# Page07_CPU_PHY.net
KiCad netlist of a schematic drawn in Altium Designer
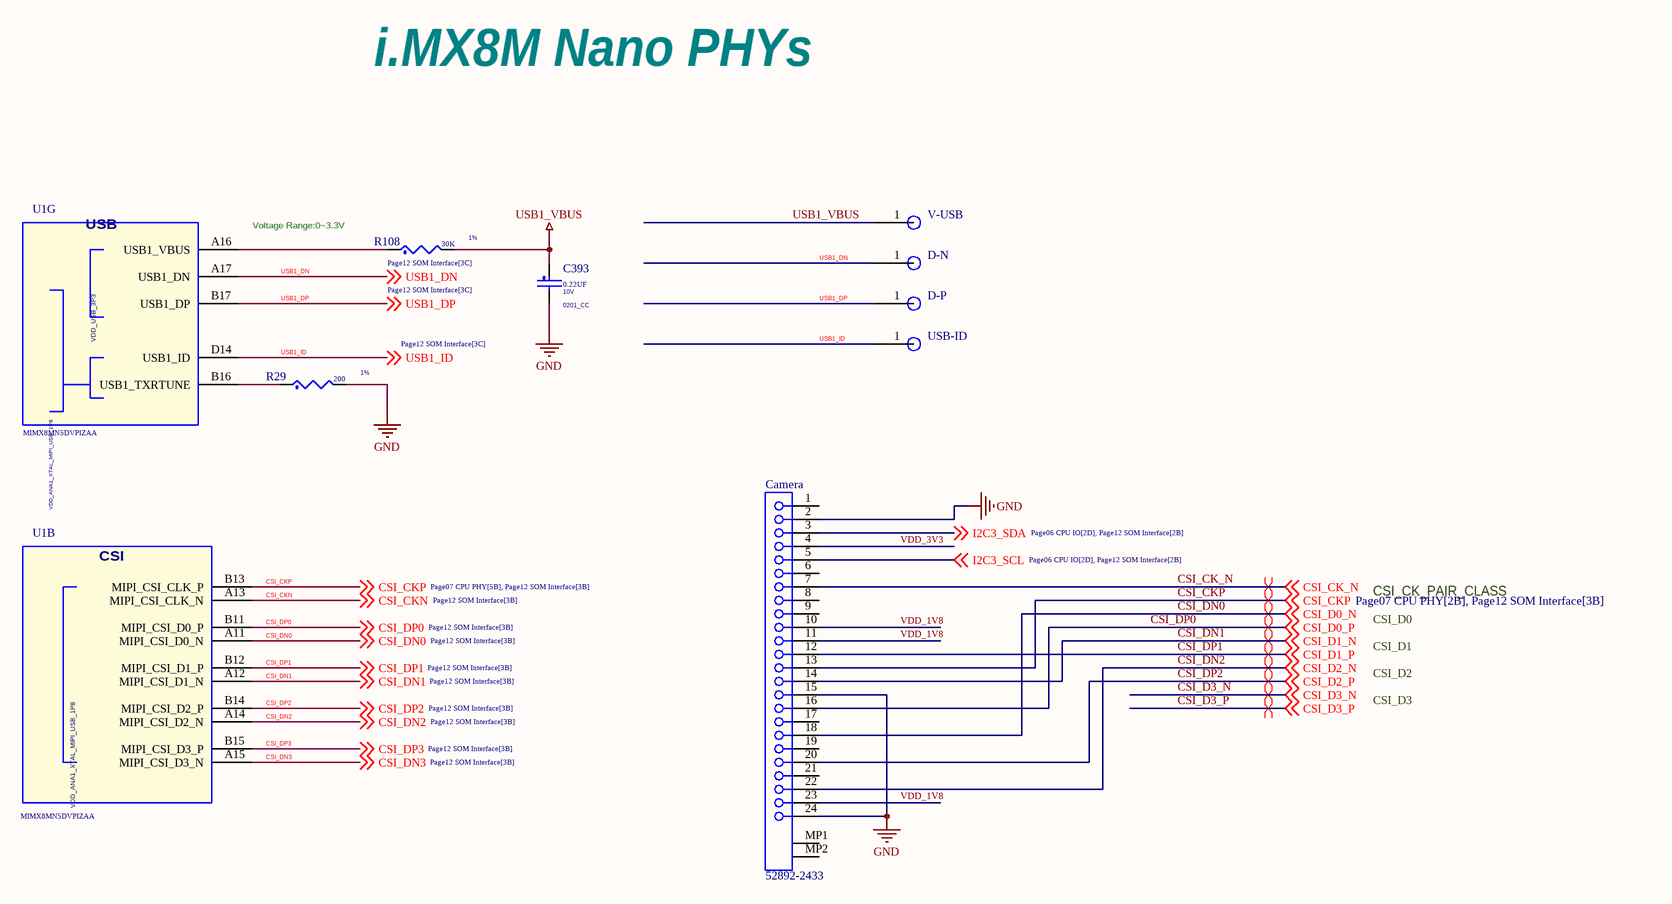
[diagram p0: Page07 CPU PHY.SchDoc]

(export (version "E")
  (design (tool "Eeschema 10.0.6"))
  (components
    (comp (ref "C393")
      (value "0.22UF")
      (footprint "0201_CC - C")
      (description "CAP CER 0.22UF 10V 20% X5R 0201")
      (fields
        (field (name "VOLTAGE") "10V")
        (field (name "TOLERANCE") "20%")
        (field (name "PCB FOOTPRINT") "0201_CC")
      )
      (libsource (lib "*") (part "CAP_NP"))
    )
    (comp (ref "Camera")
      (value "52892-2433")
      (footprint "MOLX-52892-2433")
      (fields (field (name "MANUFACTURER") "Molex"))
      (libsource (lib "Altium Content Vault") (part "MOLX-52892-2433"))
    )
    (comp (ref "D-N")
      (value "Test Pin1")
      (footprint "Test Pin")
      (libsource (lib "Altium starter project NANO") (part "Test Pin1"))
    )
    (comp (ref "D-P")
      (value "Test Pin1")
      (footprint "Test Pin")
      (libsource (lib "Altium starter project NANO") (part "Test Pin1"))
    )
    (comp (ref "R29")
      (value "200")
      (footprint "0201_RES")
      (description "RES MF 200 OHM 1/20W 1% 0201")
      (fields (field (name "TOLERANCE") "1%") (field (name "VOLTAGE") "25V"))
      (libsource (lib "*") (part "RES"))
    )
    (comp (ref "R108")
      (value "30K")
      (footprint "0201_RES")
      (description "RES MF 30K 1/20W 1% 0201")
      (fields (field (name "VOLTAGE") "25V") (field (name "TOLERANCE") "1%"))
      (libsource (lib "*") (part "RES"))
    )
    (comp (ref "U1")
      (value "MIMX8MN5DVPIZAA")
      (footprint "BGA306C50P21X21_1100X1100X101")
      (description "IC CPU QUAD CORTEX A53+M7 1.4GHZ -- BGA306")
      (libsource (lib "*") (part "MIMX8MN"))
    )
    (comp (ref "USB-ID")
      (value "Test Pin1")
      (footprint "Test Pin")
      (libsource (lib "Altium starter project NANO") (part "Test Pin1"))
    )
    (comp (ref "V-USB")
      (value "Test Pin1")
      (footprint "Test Pin")
      (libsource (lib "Altium starter project NANO") (part "Test Pin1"))
    )
  )
  (nets
    (net (code "1") (name "/VDD_1V8") (class "Default")
      (node (ref "Camera") (pin "10") (pinfunction "10_10") (pintype "passive"))
      (node (ref "Camera") (pin "11") (pinfunction "11_11") (pintype "passive"))
      (node (ref "Camera") (pin "23") (pinfunction "23_23") (pintype "passive"))
    )
    (net (code "2") (name "/VDD_3V3") (class "Default")
      (node (ref "Camera") (pin "4") (pinfunction "4_4") (pintype "passive"))
    )
    (net (code "3") (name "CSI_CKN") (class "Default")
      (node (ref "U1") (pin "A13") (pinfunction "MIPI_CSI_CLK_N_A13") (pintype "passive"))
    )
    (net (code "4") (name "CSI_CKP") (class "Default")
      (node (ref "Camera") (pin "13") (pinfunction "13_13") (pintype "passive"))
      (node (ref "U1") (pin "B13") (pinfunction "MIPI_CSI_CLK_P_B13") (pintype "passive"))
    )
    (net (code "5") (name "CSI_CK_N") (class "Default")
      (node (ref "Camera") (pin "7") (pinfunction "7_7") (pintype "passive"))
    )
    (net (code "6") (name "CSI_D0_N") (class "Default")
      (node (ref "Camera") (pin "18") (pinfunction "18_18") (pintype "passive"))
      (node (ref "U1") (pin "A11") (pinfunction "MIPI_CSI_D0_N_A11") (pintype "passive"))
    )
    (net (code "7") (name "CSI_D0_P") (class "Default")
      (node (ref "Camera") (pin "16") (pinfunction "16_16") (pintype "passive"))
      (node (ref "U1") (pin "B11") (pinfunction "MIPI_CSI_D0_P_B11") (pintype "passive"))
    )
    (net (code "8") (name "CSI_D1_N") (class "Default")
      (node (ref "Camera") (pin "14") (pinfunction "14_14") (pintype "passive"))
      (node (ref "U1") (pin "A12") (pinfunction "MIPI_CSI_D1_N_A12") (pintype "passive"))
    )
    (net (code "9") (name "CSI_D1_P") (class "Default")
      (node (ref "Camera") (pin "12") (pinfunction "12_12") (pintype "passive"))
      (node (ref "U1") (pin "B12") (pinfunction "MIPI_CSI_D1_P_B12") (pintype "passive"))
    )
    (net (code "10") (name "CSI_D2_N") (class "Default")
      (node (ref "Camera") (pin "22") (pinfunction "22_22") (pintype "passive"))
      (node (ref "U1") (pin "A14") (pinfunction "MIPI_CSI_D2_N_A14") (pintype "passive"))
    )
    (net (code "11") (name "CSI_D2_P") (class "Default")
      (node (ref "Camera") (pin "20") (pinfunction "20_20") (pintype "passive"))
      (node (ref "U1") (pin "B14") (pinfunction "MIPI_CSI_D2_P_B14") (pintype "passive"))
    )
    (net (code "14") (name "CSI_DN3") (class "Default")
      (node (ref "U1") (pin "A15") (pinfunction "MIPI_CSI_D3_N_A15") (pintype "passive"))
    )
    (net (code "15") (name "CSI_DP3") (class "Default")
      (node (ref "U1") (pin "B15") (pinfunction "MIPI_CSI_D3_P_B15") (pintype "passive"))
    )
    (net (code "16") (name "GND") (class "Default")
      (node (ref "C393") (pin "2") (pinfunction "2_2") (pintype "passive"))
      (node (ref "Camera") (pin "15") (pinfunction "15_15") (pintype "passive"))
      (node (ref "Camera") (pin "2") (pinfunction "2_2") (pintype "passive"))
      (node (ref "Camera") (pin "24") (pinfunction "24_24") (pintype "passive"))
      (node (ref "R29") (pin "2") (pinfunction "2_2") (pintype "passive"))
    )
    (net (code "17") (name "I2C3_SCL") (class "Default")
      (node (ref "Camera") (pin "5") (pinfunction "5_5") (pintype "passive"))
    )
    (net (code "18") (name "I2C3_SDA") (class "Default")
      (node (ref "Camera") (pin "3") (pinfunction "3_3") (pintype "passive"))
    )
    (net (code "19") (name "Net-(U1G-USB1_TXRTUNE)") (class "Default")
      (node (ref "R29") (pin "1") (pinfunction "1_1") (pintype "passive"))
      (node (ref "U1") (pin "B16") (pinfunction "USB1_TXRTUNE_B16") (pintype "passive"))
    )
    (net (code "20") (name "Net-(U1G-USB1_VBUS)") (class "Default")
      (node (ref "R108") (pin "1") (pinfunction "1_1") (pintype "passive"))
      (node (ref "U1") (pin "A16") (pinfunction "USB1_VBUS_A16") (pintype "passive"))
    )
    (net (code "21") (name "USB1_DN") (class "Default")
      (node (ref "D-N") (pin "1") (pinfunction "1_1") (pintype "passive"))
      (node (ref "U1") (pin "A17") (pinfunction "USB1_DN_A17") (pintype "passive"))
    )
    (net (code "22") (name "USB1_DP") (class "Default")
      (node (ref "D-P") (pin "1") (pinfunction "1_1") (pintype "passive"))
      (node (ref "U1") (pin "B17") (pinfunction "USB1_DP_B17") (pintype "passive"))
    )
    (net (code "23") (name "USB1_ID") (class "Default")
      (node (ref "U1") (pin "D14") (pinfunction "USB1_ID_D14") (pintype "passive"))
      (node (ref "USB-ID") (pin "1") (pinfunction "1_1") (pintype "passive"))
    )
    (net (code "24") (name "USB1_VBUS") (class "Default")
      (node (ref "C393") (pin "1") (pinfunction "1_1") (pintype "passive"))
      (node (ref "R108") (pin "2") (pinfunction "2_2") (pintype "passive"))
      (node (ref "V-USB") (pin "1") (pinfunction "1_1") (pintype "passive"))
    )
    (net (code "25") (name "unconnected-(Camera-Pad1)") (class "Default")
      (node (ref "Camera") (pin "1") (pinfunction "1_1") (pintype "passive"))
    )
    (net (code "26") (name "unconnected-(Camera-Pad6)") (class "Default")
      (node (ref "Camera") (pin "6") (pinfunction "6_6") (pintype "passive"))
    )
    (net (code "27") (name "unconnected-(Camera-Pad8)") (class "Default")
      (node (ref "Camera") (pin "8") (pinfunction "8_8") (pintype "passive"))
    )
    (net (code "28") (name "unconnected-(Camera-Pad9)") (class "Default")
      (node (ref "Camera") (pin "9") (pinfunction "9_9") (pintype "passive"))
    )
    (net (code "29") (name "unconnected-(Camera-Pad17)") (class "Default")
      (node (ref "Camera") (pin "17") (pinfunction "17_17") (pintype "passive"))
    )
    (net (code "30") (name "unconnected-(Camera-Pad19)") (class "Default")
      (node (ref "Camera") (pin "19") (pinfunction "19_19") (pintype "passive"))
    )
    (net (code "31") (name "unconnected-(Camera-Pad21)") (class "Default")
      (node (ref "Camera") (pin "21") (pinfunction "21_21") (pintype "passive"))
    )
    (net (code "32") (name "unconnected-(Camera-PadMP1)") (class "Default")
      (node (ref "Camera") (pin "MP1") (pinfunction "MP1_MP1") (pintype "passive"))
    )
    (net (code "33") (name "unconnected-(Camera-PadMP2)") (class "Default")
      (node (ref "Camera") (pin "MP2") (pinfunction "MP2_MP2") (pintype "passive"))
    )
  )
)
